# Sheet1.net
KiCad netlist of a schematic drawn in Altium Designer
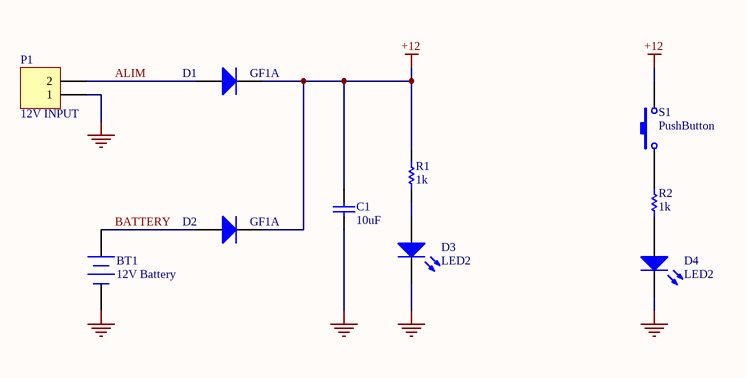
[diagram p0: Sheet1.SchDoc]

(export (version "E")
  (design (tool "Eeschema 10.0.6"))
  (components
    (comp (ref "BT1")
      (value "12V Battery")
      (footprint "BAT-2")
      (description "Multicell Battery")
      (fields (field (name "PUBLISHER") "Altium Limited"))
      (libsource (lib "Miscellaneous Devices") (part "Battery"))
    )
    (comp (ref "C1")
      (value "10uF")
      (footprint "RAD-0.3")
      (description "Capacitor")
      (fields (field (name "PUBLISHER") "Altium Limited"))
      (libsource (lib "Miscellaneous Devices") (part "Cap"))
    )
    (comp (ref "D1")
      (value "GF1A")
      (footprint "SMC")
      (description "Default Diode")
      (fields (field (name "PUBLISHER") "Altium Limited"))
      (libsource (lib "Miscellaneous Devices") (part "Diode"))
    )
    (comp (ref "D2")
      (value "GF1A")
      (footprint "SMC")
      (description "Default Diode")
      (fields (field (name "PUBLISHER") "Altium Limited"))
      (libsource (lib "Miscellaneous Devices") (part "Diode"))
    )
    (comp (ref "D3")
      (value "LED2")
      (footprint "3.2X1.6X1.1")
      (description "Typical RED, GREEN, YELLOW, AMBER GaAs LED")
      (fields (field (name "PUBLISHER") "Altium Limited"))
      (libsource (lib "Miscellaneous Devices") (part "LED2"))
    )
    (comp (ref "D4")
      (value "LED2")
      (footprint "3.2X1.6X1.1")
      (description "Typical RED, GREEN, YELLOW, AMBER GaAs LED")
      (fields (field (name "PUBLISHER") "Altium Limited"))
      (libsource (lib "Miscellaneous Devices") (part "LED2"))
    )
    (comp (ref "P1")
      (value "12V INPUT")
      (footprint "HDR1X2")
      (description "Header, 2-Pin")
      (fields (field (name "PUBLISHER") "Altium Limited"))
      (libsource (lib "Miscellaneous Connectors") (part "Header 2"))
    )
    (comp (ref "R1")
      (value "1k")
      (footprint "AXIAL-0.3")
      (description "Resistor")
      (fields (field (name "PUBLISHER") "Altium Limited"))
      (libsource (lib "Miscellaneous Devices") (part "Res1"))
    )
    (comp (ref "R2")
      (value "1k")
      (footprint "AXIAL-0.3")
      (description "Resistor")
      (fields (field (name "PUBLISHER") "Altium Limited"))
      (libsource (lib "Miscellaneous Devices") (part "Res1"))
    )
    (comp (ref "S1")
      (value "PushButton")
      (footprint "SPST-2")
      (description "Switch")
      (fields (field (name "PUBLISHER") "Altium Limited"))
      (libsource (lib "Miscellaneous Devices") (part "SW-PB"))
    )
  )
  (nets
    (net (code "1") (name "+12") (class "Default")
      (node (ref "C1") (pin "2") (pinfunction "2_2") (pintype "passive"))
      (node (ref "D1") (pin "2") (pinfunction "K_2") (pintype "passive"))
      (node (ref "D2") (pin "2") (pinfunction "K_2") (pintype "passive"))
      (node (ref "R1") (pin "2") (pinfunction "2_2") (pintype "passive"))
      (node (ref "S1") (pin "2") (pinfunction "2_2") (pintype "passive"))
    )
    (net (code "2") (name "/ALIM") (class "Default")
      (node (ref "D1") (pin "1") (pinfunction "A_1") (pintype "passive"))
      (node (ref "P1") (pin "2") (pinfunction "2_2") (pintype "passive"))
    )
    (net (code "3") (name "/BATTERY") (class "Default")
      (node (ref "BT1") (pin "1") (pinfunction "+_1") (pintype "passive"))
      (node (ref "D2") (pin "1") (pinfunction "A_1") (pintype "passive"))
    )
    (net (code "4") (name "GND") (class "Default")
      (node (ref "BT1") (pin "2") (pinfunction "-_2") (pintype "passive"))
      (node (ref "C1") (pin "1") (pinfunction "1_1") (pintype "passive"))
      (node (ref "D3") (pin "2") (pinfunction "K_2") (pintype "passive"))
      (node (ref "D4") (pin "2") (pinfunction "K_2") (pintype "passive"))
      (node (ref "P1") (pin "1") (pinfunction "1_1") (pintype "passive"))
    )
    (net (code "5") (name "Net-(D3-A)") (class "Default")
      (node (ref "D3") (pin "1") (pinfunction "A_1") (pintype "passive"))
      (node (ref "R1") (pin "1") (pinfunction "1_1") (pintype "passive"))
    )
    (net (code "6") (name "Net-(D4-A)") (class "Default")
      (node (ref "D4") (pin "1") (pinfunction "A_1") (pintype "passive"))
      (node (ref "R2") (pin "1") (pinfunction "1_1") (pintype "passive"))
    )
    (net (code "7") (name "Net-(R2-Pad2)") (class "Default")
      (node (ref "R2") (pin "2") (pinfunction "2_2") (pintype "passive"))
      (node (ref "S1") (pin "1") (pinfunction "1_1") (pintype "passive"))
    )
  )
)
